# Q23_BRAKE_LIGHT.net
KiCad netlist of a schematic drawn in Altium Designer
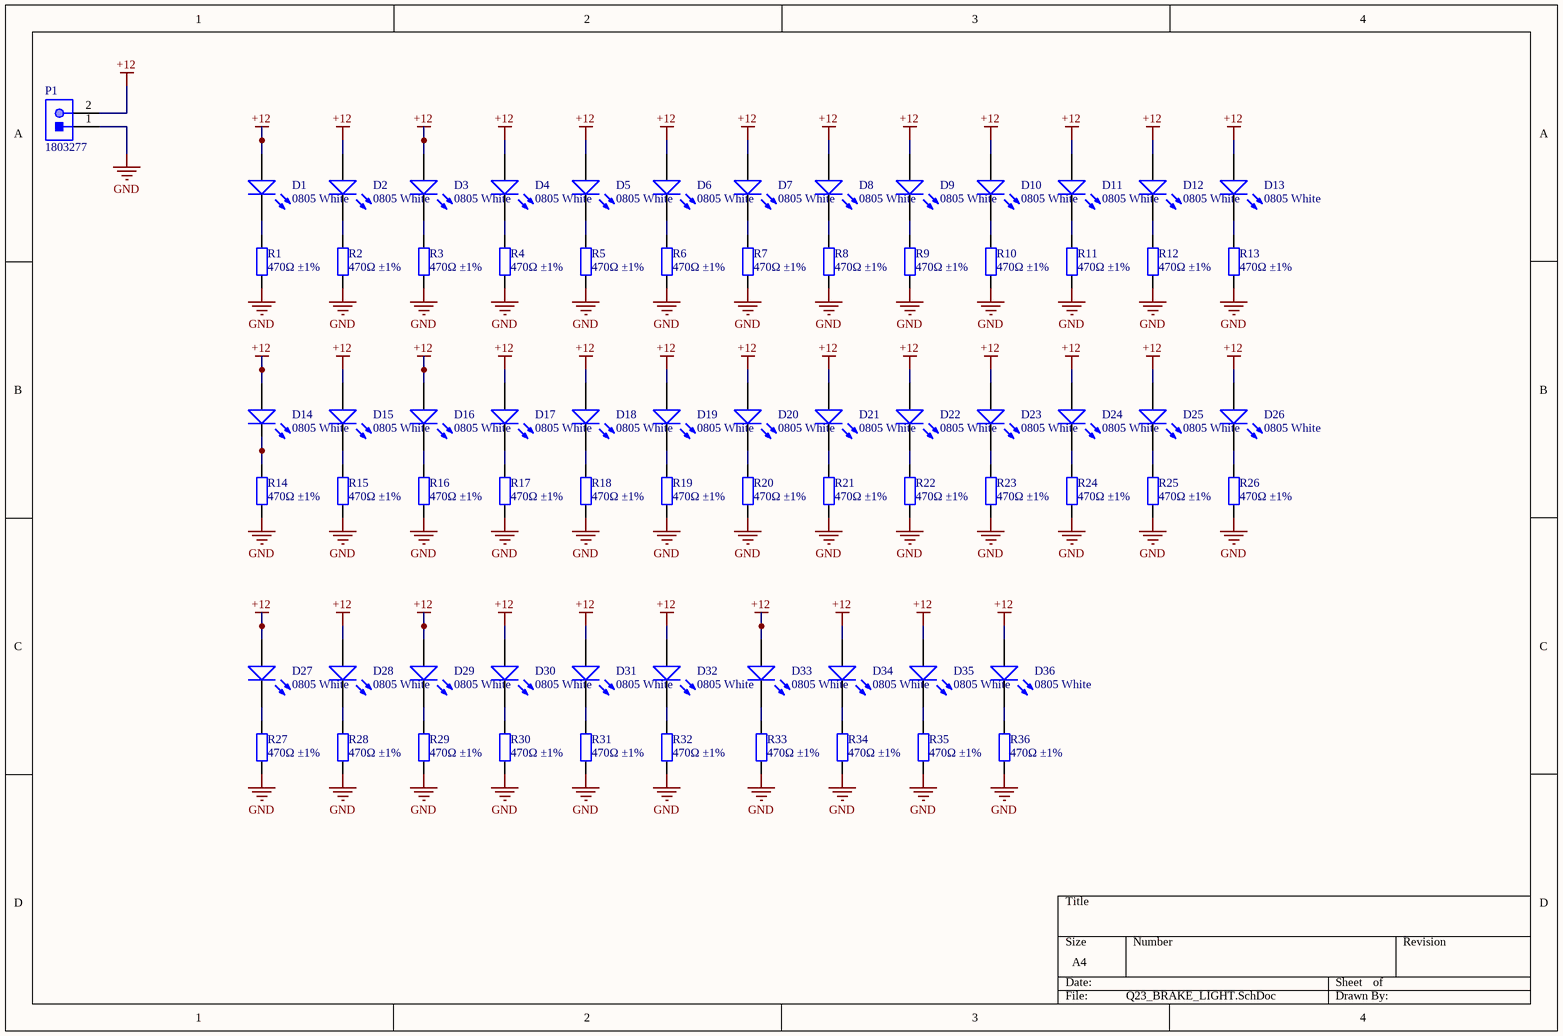
[diagram p0: Q23_BRAKE_LIGHT.SchDoc]

(export (version "E")
  (design (tool "Eeschema 10.0.6"))
  (components
    (comp (ref "D1")
      (value "0805 White")
      (footprint "0805_LED_S1")
      (description "LED")
      (libsource (lib "LED") (part "0805 LED White"))
    )
    (comp (ref "D2")
      (value "0805 White")
      (footprint "0805_LED_S1")
      (description "LED")
      (libsource (lib "LED") (part "0805 LED White"))
    )
    (comp (ref "D3")
      (value "0805 White")
      (footprint "0805_LED_S1")
      (description "LED")
      (libsource (lib "LED") (part "0805 LED White"))
    )
    (comp (ref "D4")
      (value "0805 White")
      (footprint "0805_LED_S1")
      (description "LED")
      (libsource (lib "LED") (part "0805 LED White"))
    )
    (comp (ref "D5")
      (value "0805 White")
      (footprint "0805_LED_S1")
      (description "LED")
      (libsource (lib "LED") (part "0805 LED White"))
    )
    (comp (ref "D6")
      (value "0805 White")
      (footprint "0805_LED_S1")
      (description "LED")
      (libsource (lib "LED") (part "0805 LED White"))
    )
    (comp (ref "D7")
      (value "0805 White")
      (footprint "0805_LED_S1")
      (description "LED")
      (libsource (lib "LED") (part "0805 LED White"))
    )
    (comp (ref "D8")
      (value "0805 White")
      (footprint "0805_LED_S1")
      (description "LED")
      (libsource (lib "LED") (part "0805 LED White"))
    )
    (comp (ref "D9")
      (value "0805 White")
      (footprint "0805_LED_S1")
      (description "LED")
      (libsource (lib "LED") (part "0805 LED White"))
    )
    (comp (ref "D10")
      (value "0805 White")
      (footprint "0805_LED_S1")
      (description "LED")
      (libsource (lib "LED") (part "0805 LED White"))
    )
    (comp (ref "D11")
      (value "0805 White")
      (footprint "0805_LED_S1")
      (description "LED")
      (libsource (lib "LED") (part "0805 LED White"))
    )
    (comp (ref "D12")
      (value "0805 White")
      (footprint "0805_LED_S1")
      (description "LED")
      (libsource (lib "LED") (part "0805 LED White"))
    )
    (comp (ref "D13")
      (value "0805 White")
      (footprint "0805_LED_S1")
      (description "LED")
      (libsource (lib "LED") (part "0805 LED White"))
    )
    (comp (ref "D14")
      (value "0805 White")
      (footprint "0805_LED_S1")
      (description "LED")
      (libsource (lib "LED") (part "0805 LED White"))
    )
    (comp (ref "D15")
      (value "0805 White")
      (footprint "0805_LED_S1")
      (description "LED")
      (libsource (lib "LED") (part "0805 LED White"))
    )
    (comp (ref "D16")
      (value "0805 White")
      (footprint "0805_LED_S1")
      (description "LED")
      (libsource (lib "LED") (part "0805 LED White"))
    )
    (comp (ref "D17")
      (value "0805 White")
      (footprint "0805_LED_S1")
      (description "LED")
      (libsource (lib "LED") (part "0805 LED White"))
    )
    (comp (ref "D18")
      (value "0805 White")
      (footprint "0805_LED_S1")
      (description "LED")
      (libsource (lib "LED") (part "0805 LED White"))
    )
    (comp (ref "D19")
      (value "0805 White")
      (footprint "0805_LED_S1")
      (description "LED")
      (libsource (lib "LED") (part "0805 LED White"))
    )
    (comp (ref "D20")
      (value "0805 White")
      (footprint "0805_LED_S1")
      (description "LED")
      (libsource (lib "LED") (part "0805 LED White"))
    )
    (comp (ref "D21")
      (value "0805 White")
      (footprint "0805_LED_S1")
      (description "LED")
      (libsource (lib "LED") (part "0805 LED White"))
    )
    (comp (ref "D22")
      (value "0805 White")
      (footprint "0805_LED_S1")
      (description "LED")
      (libsource (lib "LED") (part "0805 LED White"))
    )
    (comp (ref "D23")
      (value "0805 White")
      (footprint "0805_LED_S1")
      (description "LED")
      (libsource (lib "LED") (part "0805 LED White"))
    )
    (comp (ref "D24")
      (value "0805 White")
      (footprint "0805_LED_S1")
      (description "LED")
      (libsource (lib "LED") (part "0805 LED White"))
    )
    (comp (ref "D25")
      (value "0805 White")
      (footprint "0805_LED_S1")
      (description "LED")
      (libsource (lib "LED") (part "0805 LED White"))
    )
    (comp (ref "D26")
      (value "0805 White")
      (footprint "0805_LED_S1")
      (description "LED")
      (libsource (lib "LED") (part "0805 LED White"))
    )
    (comp (ref "D27")
      (value "0805 White")
      (footprint "0805_LED_S1")
      (description "LED")
      (libsource (lib "LED") (part "0805 LED White"))
    )
    (comp (ref "D28")
      (value "0805 White")
      (footprint "0805_LED_S1")
      (description "LED")
      (libsource (lib "LED") (part "0805 LED White"))
    )
    (comp (ref "D29")
      (value "0805 White")
      (footprint "0805_LED_S1")
      (description "LED")
      (libsource (lib "LED") (part "0805 LED White"))
    )
    (comp (ref "D30")
      (value "0805 White")
      (footprint "0805_LED_S1")
      (description "LED")
      (libsource (lib "LED") (part "0805 LED White"))
    )
    (comp (ref "D31")
      (value "0805 White")
      (footprint "0805_LED_S1")
      (description "LED")
      (libsource (lib "LED") (part "0805 LED White"))
    )
    (comp (ref "D32")
      (value "0805 White")
      (footprint "0805_LED_S1")
      (description "LED")
      (libsource (lib "LED") (part "0805 LED White"))
    )
    (comp (ref "D33")
      (value "0805 White")
      (footprint "0805_LED_S1")
      (description "LED")
      (libsource (lib "LED") (part "0805 LED White"))
    )
    (comp (ref "D34")
      (value "0805 White")
      (footprint "0805_LED_S1")
      (description "LED")
      (libsource (lib "LED") (part "0805 LED White"))
    )
    (comp (ref "D35")
      (value "0805 White")
      (footprint "0805_LED_S1")
      (description "LED")
      (libsource (lib "LED") (part "0805 LED White"))
    )
    (comp (ref "D36")
      (value "0805 White")
      (footprint "0805_LED_S1")
      (description "LED")
      (libsource (lib "LED") (part "0805 LED White"))
    )
    (comp (ref "P1")
      (value "1803277")
      (footprint "PHOE-1803277_V")
      (description "Male Header, Pitch 3.81 mm, 1 x 2 Position, Height 7.25 mm, Tail Length 3.4 mm, RoHS, Bulk")
      (fields (field (name "MANUFACTURER") "Phoenix Contact"))
      (libsource (lib "Americas- FSAE- Queens University") (part "CN-1P-M-R2"))
    )
    (comp (ref "R1")
      (value "470Ω ±1%")
      (footprint "0402_R")
      (description "Chip resistor")
      (fields (field (name "MANUFACTURER") "Uniroyal Elec") (field (name "PARTNUMBER") "0402WGF4700TCE"))
      (libsource (lib "RES") (part "0402 470R (4700) 1%"))
    )
    (comp (ref "R2")
      (value "470Ω ±1%")
      (footprint "0402_R")
      (description "Chip resistor")
      (fields (field (name "MANUFACTURER") "Uniroyal Elec") (field (name "PARTNUMBER") "0402WGF4700TCE"))
      (libsource (lib "RES") (part "0402 470R (4700) 1%"))
    )
    (comp (ref "R3")
      (value "470Ω ±1%")
      (footprint "0402_R")
      (description "Chip resistor")
      (fields (field (name "MANUFACTURER") "Uniroyal Elec") (field (name "PARTNUMBER") "0402WGF4700TCE"))
      (libsource (lib "RES") (part "0402 470R (4700) 1%"))
    )
    (comp (ref "R4")
      (value "470Ω ±1%")
      (footprint "0402_R")
      (description "Chip resistor")
      (fields (field (name "MANUFACTURER") "Uniroyal Elec") (field (name "PARTNUMBER") "0402WGF4700TCE"))
      (libsource (lib "RES") (part "0402 470R (4700) 1%"))
    )
    (comp (ref "R5")
      (value "470Ω ±1%")
      (footprint "0402_R")
      (description "Chip resistor")
      (fields (field (name "MANUFACTURER") "Uniroyal Elec") (field (name "PARTNUMBER") "0402WGF4700TCE"))
      (libsource (lib "RES") (part "0402 470R (4700) 1%"))
    )
    (comp (ref "R6")
      (value "470Ω ±1%")
      (footprint "0402_R")
      (description "Chip resistor")
      (fields (field (name "MANUFACTURER") "Uniroyal Elec") (field (name "PARTNUMBER") "0402WGF4700TCE"))
      (libsource (lib "RES") (part "0402 470R (4700) 1%"))
    )
    (comp (ref "R7")
      (value "470Ω ±1%")
      (footprint "0402_R")
      (description "Chip resistor")
      (fields (field (name "MANUFACTURER") "Uniroyal Elec") (field (name "PARTNUMBER") "0402WGF4700TCE"))
      (libsource (lib "RES") (part "0402 470R (4700) 1%"))
    )
    (comp (ref "R8")
      (value "470Ω ±1%")
      (footprint "0402_R")
      (description "Chip resistor")
      (fields (field (name "MANUFACTURER") "Uniroyal Elec") (field (name "PARTNUMBER") "0402WGF4700TCE"))
      (libsource (lib "RES") (part "0402 470R (4700) 1%"))
    )
    (comp (ref "R9")
      (value "470Ω ±1%")
      (footprint "0402_R")
      (description "Chip resistor")
      (fields (field (name "MANUFACTURER") "Uniroyal Elec") (field (name "PARTNUMBER") "0402WGF4700TCE"))
      (libsource (lib "RES") (part "0402 470R (4700) 1%"))
    )
    (comp (ref "R10")
      (value "470Ω ±1%")
      (footprint "0402_R")
      (description "Chip resistor")
      (fields (field (name "MANUFACTURER") "Uniroyal Elec") (field (name "PARTNUMBER") "0402WGF4700TCE"))
      (libsource (lib "RES") (part "0402 470R (4700) 1%"))
    )
    (comp (ref "R11")
      (value "470Ω ±1%")
      (footprint "0402_R")
      (description "Chip resistor")
      (fields (field (name "MANUFACTURER") "Uniroyal Elec") (field (name "PARTNUMBER") "0402WGF4700TCE"))
      (libsource (lib "RES") (part "0402 470R (4700) 1%"))
    )
    (comp (ref "R12")
      (value "470Ω ±1%")
      (footprint "0402_R")
      (description "Chip resistor")
      (fields (field (name "MANUFACTURER") "Uniroyal Elec") (field (name "PARTNUMBER") "0402WGF4700TCE"))
      (libsource (lib "RES") (part "0402 470R (4700) 1%"))
    )
    (comp (ref "R13")
      (value "470Ω ±1%")
      (footprint "0402_R")
      (description "Chip resistor")
      (fields (field (name "MANUFACTURER") "Uniroyal Elec") (field (name "PARTNUMBER") "0402WGF4700TCE"))
      (libsource (lib "RES") (part "0402 470R (4700) 1%"))
    )
    (comp (ref "R14")
      (value "470Ω ±1%")
      (footprint "0402_R")
      (description "Chip resistor")
      (fields (field (name "MANUFACTURER") "Uniroyal Elec") (field (name "PARTNUMBER") "0402WGF4700TCE"))
      (libsource (lib "RES") (part "0402 470R (4700) 1%"))
    )
    (comp (ref "R15")
      (value "470Ω ±1%")
      (footprint "0402_R")
      (description "Chip resistor")
      (fields (field (name "MANUFACTURER") "Uniroyal Elec") (field (name "PARTNUMBER") "0402WGF4700TCE"))
      (libsource (lib "RES") (part "0402 470R (4700) 1%"))
    )
    (comp (ref "R16")
      (value "470Ω ±1%")
      (footprint "0402_R")
      (description "Chip resistor")
      (fields (field (name "MANUFACTURER") "Uniroyal Elec") (field (name "PARTNUMBER") "0402WGF4700TCE"))
      (libsource (lib "RES") (part "0402 470R (4700) 1%"))
    )
    (comp (ref "R17")
      (value "470Ω ±1%")
      (footprint "0402_R")
      (description "Chip resistor")
      (fields (field (name "MANUFACTURER") "Uniroyal Elec") (field (name "PARTNUMBER") "0402WGF4700TCE"))
      (libsource (lib "RES") (part "0402 470R (4700) 1%"))
    )
    (comp (ref "R18")
      (value "470Ω ±1%")
      (footprint "0402_R")
      (description "Chip resistor")
      (fields (field (name "MANUFACTURER") "Uniroyal Elec") (field (name "PARTNUMBER") "0402WGF4700TCE"))
      (libsource (lib "RES") (part "0402 470R (4700) 1%"))
    )
    (comp (ref "R19")
      (value "470Ω ±1%")
      (footprint "0402_R")
      (description "Chip resistor")
      (fields (field (name "MANUFACTURER") "Uniroyal Elec") (field (name "PARTNUMBER") "0402WGF4700TCE"))
      (libsource (lib "RES") (part "0402 470R (4700) 1%"))
    )
    (comp (ref "R20")
      (value "470Ω ±1%")
      (footprint "0402_R")
      (description "Chip resistor")
      (fields (field (name "MANUFACTURER") "Uniroyal Elec") (field (name "PARTNUMBER") "0402WGF4700TCE"))
      (libsource (lib "RES") (part "0402 470R (4700) 1%"))
    )
    (comp (ref "R21")
      (value "470Ω ±1%")
      (footprint "0402_R")
      (description "Chip resistor")
      (fields (field (name "MANUFACTURER") "Uniroyal Elec") (field (name "PARTNUMBER") "0402WGF4700TCE"))
      (libsource (lib "RES") (part "0402 470R (4700) 1%"))
    )
    (comp (ref "R22")
      (value "470Ω ±1%")
      (footprint "0402_R")
      (description "Chip resistor")
      (fields (field (name "MANUFACTURER") "Uniroyal Elec") (field (name "PARTNUMBER") "0402WGF4700TCE"))
      (libsource (lib "RES") (part "0402 470R (4700) 1%"))
    )
    (comp (ref "R23")
      (value "470Ω ±1%")
      (footprint "0402_R")
      (description "Chip resistor")
      (fields (field (name "MANUFACTURER") "Uniroyal Elec") (field (name "PARTNUMBER") "0402WGF4700TCE"))
      (libsource (lib "RES") (part "0402 470R (4700) 1%"))
    )
    (comp (ref "R24")
      (value "470Ω ±1%")
      (footprint "0402_R")
      (description "Chip resistor")
      (fields (field (name "MANUFACTURER") "Uniroyal Elec") (field (name "PARTNUMBER") "0402WGF4700TCE"))
      (libsource (lib "RES") (part "0402 470R (4700) 1%"))
    )
    (comp (ref "R25")
      (value "470Ω ±1%")
      (footprint "0402_R")
      (description "Chip resistor")
      (fields (field (name "MANUFACTURER") "Uniroyal Elec") (field (name "PARTNUMBER") "0402WGF4700TCE"))
      (libsource (lib "RES") (part "0402 470R (4700) 1%"))
    )
    (comp (ref "R26")
      (value "470Ω ±1%")
      (footprint "0402_R")
      (description "Chip resistor")
      (fields (field (name "MANUFACTURER") "Uniroyal Elec") (field (name "PARTNUMBER") "0402WGF4700TCE"))
      (libsource (lib "RES") (part "0402 470R (4700) 1%"))
    )
    (comp (ref "R27")
      (value "470Ω ±1%")
      (footprint "0402_R")
      (description "Chip resistor")
      (fields (field (name "MANUFACTURER") "Uniroyal Elec") (field (name "PARTNUMBER") "0402WGF4700TCE"))
      (libsource (lib "RES") (part "0402 470R (4700) 1%"))
    )
    (comp (ref "R28")
      (value "470Ω ±1%")
      (footprint "0402_R")
      (description "Chip resistor")
      (fields (field (name "MANUFACTURER") "Uniroyal Elec") (field (name "PARTNUMBER") "0402WGF4700TCE"))
      (libsource (lib "RES") (part "0402 470R (4700) 1%"))
    )
    (comp (ref "R29")
      (value "470Ω ±1%")
      (footprint "0402_R")
      (description "Chip resistor")
      (fields (field (name "MANUFACTURER") "Uniroyal Elec") (field (name "PARTNUMBER") "0402WGF4700TCE"))
      (libsource (lib "RES") (part "0402 470R (4700) 1%"))
    )
    (comp (ref "R30")
      (value "470Ω ±1%")
      (footprint "0402_R")
      (description "Chip resistor")
      (fields (field (name "MANUFACTURER") "Uniroyal Elec") (field (name "PARTNUMBER") "0402WGF4700TCE"))
      (libsource (lib "RES") (part "0402 470R (4700) 1%"))
    )
    (comp (ref "R31")
      (value "470Ω ±1%")
      (footprint "0402_R")
      (description "Chip resistor")
      (fields (field (name "MANUFACTURER") "Uniroyal Elec") (field (name "PARTNUMBER") "0402WGF4700TCE"))
      (libsource (lib "RES") (part "0402 470R (4700) 1%"))
    )
    (comp (ref "R32")
      (value "470Ω ±1%")
      (footprint "0402_R")
      (description "Chip resistor")
      (fields (field (name "MANUFACTURER") "Uniroyal Elec") (field (name "PARTNUMBER") "0402WGF4700TCE"))
      (libsource (lib "RES") (part "0402 470R (4700) 1%"))
    )
    (comp (ref "R33")
      (value "470Ω ±1%")
      (footprint "0402_R")
      (description "Chip resistor")
      (fields (field (name "MANUFACTURER") "Uniroyal Elec") (field (name "PARTNUMBER") "0402WGF4700TCE"))
      (libsource (lib "RES") (part "0402 470R (4700) 1%"))
    )
    (comp (ref "R34")
      (value "470Ω ±1%")
      (footprint "0402_R")
      (description "Chip resistor")
      (fields (field (name "MANUFACTURER") "Uniroyal Elec") (field (name "PARTNUMBER") "0402WGF4700TCE"))
      (libsource (lib "RES") (part "0402 470R (4700) 1%"))
    )
    (comp (ref "R35")
      (value "470Ω ±1%")
      (footprint "0402_R")
      (description "Chip resistor")
      (fields (field (name "MANUFACTURER") "Uniroyal Elec") (field (name "PARTNUMBER") "0402WGF4700TCE"))
      (libsource (lib "RES") (part "0402 470R (4700) 1%"))
    )
    (comp (ref "R36")
      (value "470Ω ±1%")
      (footprint "0402_R")
      (description "Chip resistor")
      (fields (field (name "MANUFACTURER") "Uniroyal Elec") (field (name "PARTNUMBER") "0402WGF4700TCE"))
      (libsource (lib "RES") (part "0402 470R (4700) 1%"))
    )
  )
  (nets
    (net (code "1") (name "+12") (class "Default")
      (node (ref "D1") (pin "A") (pinfunction "A_A") (pintype "passive"))
      (node (ref "D10") (pin "A") (pinfunction "A_A") (pintype "passive"))
      (node (ref "D11") (pin "A") (pinfunction "A_A") (pintype "passive"))
      (node (ref "D12") (pin "A") (pinfunction "A_A") (pintype "passive"))
      (node (ref "D13") (pin "A") (pinfunction "A_A") (pintype "passive"))
      (node (ref "D14") (pin "A") (pinfunction "A_A") (pintype "passive"))
      (node (ref "D15") (pin "A") (pinfunction "A_A") (pintype "passive"))
      (node (ref "D16") (pin "A") (pinfunction "A_A") (pintype "passive"))
      (node (ref "D17") (pin "A") (pinfunction "A_A") (pintype "passive"))
      (node (ref "D18") (pin "A") (pinfunction "A_A") (pintype "passive"))
      (node (ref "D19") (pin "A") (pinfunction "A_A") (pintype "passive"))
      (node (ref "D2") (pin "A") (pinfunction "A_A") (pintype "passive"))
      (node (ref "D20") (pin "A") (pinfunction "A_A") (pintype "passive"))
      (node (ref "D21") (pin "A") (pinfunction "A_A") (pintype "passive"))
      (node (ref "D22") (pin "A") (pinfunction "A_A") (pintype "passive"))
      (node (ref "D23") (pin "A") (pinfunction "A_A") (pintype "passive"))
      (node (ref "D24") (pin "A") (pinfunction "A_A") (pintype "passive"))
      (node (ref "D25") (pin "A") (pinfunction "A_A") (pintype "passive"))
      (node (ref "D26") (pin "A") (pinfunction "A_A") (pintype "passive"))
      (node (ref "D27") (pin "A") (pinfunction "A_A") (pintype "passive"))
      (node (ref "D28") (pin "A") (pinfunction "A_A") (pintype "passive"))
      (node (ref "D29") (pin "A") (pinfunction "A_A") (pintype "passive"))
      (node (ref "D3") (pin "A") (pinfunction "A_A") (pintype "passive"))
      (node (ref "D30") (pin "A") (pinfunction "A_A") (pintype "passive"))
      (node (ref "D31") (pin "A") (pinfunction "A_A") (pintype "passive"))
      (node (ref "D32") (pin "A") (pinfunction "A_A") (pintype "passive"))
      (node (ref "D33") (pin "A") (pinfunction "A_A") (pintype "passive"))
      (node (ref "D34") (pin "A") (pinfunction "A_A") (pintype "passive"))
      (node (ref "D35") (pin "A") (pinfunction "A_A") (pintype "passive"))
      (node (ref "D36") (pin "A") (pinfunction "A_A") (pintype "passive"))
      (node (ref "D4") (pin "A") (pinfunction "A_A") (pintype "passive"))
      (node (ref "D5") (pin "A") (pinfunction "A_A") (pintype "passive"))
      (node (ref "D6") (pin "A") (pinfunction "A_A") (pintype "passive"))
      (node (ref "D7") (pin "A") (pinfunction "A_A") (pintype "passive"))
      (node (ref "D8") (pin "A") (pinfunction "A_A") (pintype "passive"))
      (node (ref "D9") (pin "A") (pinfunction "A_A") (pintype "passive"))
      (node (ref "P1") (pin "2") (pinfunction "2_2") (pintype "passive"))
    )
    (net (code "2") (name "GND") (class "Default")
      (node (ref "P1") (pin "1") (pinfunction "1_1") (pintype "passive"))
      (node (ref "R1") (pin "1") (pinfunction "1_1") (pintype "passive"))
      (node (ref "R10") (pin "1") (pinfunction "1_1") (pintype "passive"))
      (node (ref "R11") (pin "1") (pinfunction "1_1") (pintype "passive"))
      (node (ref "R12") (pin "1") (pinfunction "1_1") (pintype "passive"))
      (node (ref "R13") (pin "1") (pinfunction "1_1") (pintype "passive"))
      (node (ref "R14") (pin "1") (pinfunction "1_1") (pintype "passive"))
      (node (ref "R15") (pin "1") (pinfunction "1_1") (pintype "passive"))
      (node (ref "R16") (pin "1") (pinfunction "1_1") (pintype "passive"))
      (node (ref "R17") (pin "1") (pinfunction "1_1") (pintype "passive"))
      (node (ref "R18") (pin "1") (pinfunction "1_1") (pintype "passive"))
      (node (ref "R19") (pin "1") (pinfunction "1_1") (pintype "passive"))
      (node (ref "R2") (pin "1") (pinfunction "1_1") (pintype "passive"))
      (node (ref "R20") (pin "1") (pinfunction "1_1") (pintype "passive"))
      (node (ref "R21") (pin "1") (pinfunction "1_1") (pintype "passive"))
      (node (ref "R22") (pin "1") (pinfunction "1_1") (pintype "passive"))
      (node (ref "R23") (pin "1") (pinfunction "1_1") (pintype "passive"))
      (node (ref "R24") (pin "1") (pinfunction "1_1") (pintype "passive"))
      (node (ref "R25") (pin "1") (pinfunction "1_1") (pintype "passive"))
      (node (ref "R26") (pin "1") (pinfunction "1_1") (pintype "passive"))
      (node (ref "R27") (pin "1") (pinfunction "1_1") (pintype "passive"))
      (node (ref "R28") (pin "1") (pinfunction "1_1") (pintype "passive"))
      (node (ref "R29") (pin "1") (pinfunction "1_1") (pintype "passive"))
      (node (ref "R3") (pin "1") (pinfunction "1_1") (pintype "passive"))
      (node (ref "R30") (pin "1") (pinfunction "1_1") (pintype "passive"))
      (node (ref "R31") (pin "1") (pinfunction "1_1") (pintype "passive"))
      (node (ref "R32") (pin "1") (pinfunction "1_1") (pintype "passive"))
      (node (ref "R33") (pin "1") (pinfunction "1_1") (pintype "passive"))
      (node (ref "R34") (pin "1") (pinfunction "1_1") (pintype "passive"))
      (node (ref "R35") (pin "1") (pinfunction "1_1") (pintype "passive"))
      (node (ref "R36") (pin "1") (pinfunction "1_1") (pintype "passive"))
      (node (ref "R4") (pin "1") (pinfunction "1_1") (pintype "passive"))
      (node (ref "R5") (pin "1") (pinfunction "1_1") (pintype "passive"))
      (node (ref "R6") (pin "1") (pinfunction "1_1") (pintype "passive"))
      (node (ref "R7") (pin "1") (pinfunction "1_1") (pintype "passive"))
      (node (ref "R8") (pin "1") (pinfunction "1_1") (pintype "passive"))
      (node (ref "R9") (pin "1") (pinfunction "1_1") (pintype "passive"))
    )
    (net (code "3") (name "Net-(D1-PadK)") (class "Default")
      (node (ref "D1") (pin "K") (pinfunction "K_K") (pintype "passive"))
      (node (ref "R1") (pin "2") (pinfunction "2_2") (pintype "passive"))
    )
    (net (code "4") (name "Net-(D2-PadK)") (class "Default")
      (node (ref "D2") (pin "K") (pinfunction "K_K") (pintype "passive"))
      (node (ref "R2") (pin "2") (pinfunction "2_2") (pintype "passive"))
    )
    (net (code "5") (name "Net-(D3-PadK)") (class "Default")
      (node (ref "D3") (pin "K") (pinfunction "K_K") (pintype "passive"))
      (node (ref "R3") (pin "2") (pinfunction "2_2") (pintype "passive"))
    )
    (net (code "6") (name "Net-(D4-PadK)") (class "Default")
      (node (ref "D4") (pin "K") (pinfunction "K_K") (pintype "passive"))
      (node (ref "R4") (pin "2") (pinfunction "2_2") (pintype "passive"))
    )
    (net (code "7") (name "Net-(D5-PadK)") (class "Default")
      (node (ref "D5") (pin "K") (pinfunction "K_K") (pintype "passive"))
      (node (ref "R5") (pin "2") (pinfunction "2_2") (pintype "passive"))
    )
    (net (code "8") (name "Net-(D6-PadK)") (class "Default")
      (node (ref "D6") (pin "K") (pinfunction "K_K") (pintype "passive"))
      (node (ref "R6") (pin "2") (pinfunction "2_2") (pintype "passive"))
    )
    (net (code "9") (name "Net-(D7-PadK)") (class "Default")
      (node (ref "D7") (pin "K") (pinfunction "K_K") (pintype "passive"))
      (node (ref "R7") (pin "2") (pinfunction "2_2") (pintype "passive"))
    )
    (net (code "10") (name "Net-(D8-PadK)") (class "Default")
      (node (ref "D8") (pin "K") (pinfunction "K_K") (pintype "passive"))
      (node (ref "R8") (pin "2") (pinfunction "2_2") (pintype "passive"))
    )
    (net (code "11") (name "Net-(D9-PadK)") (class "Default")
      (node (ref "D9") (pin "K") (pinfunction "K_K") (pintype "passive"))
      (node (ref "R9") (pin "2") (pinfunction "2_2") (pintype "passive"))
    )
    (net (code "12") (name "Net-(D10-PadK)") (class "Default")
      (node (ref "D10") (pin "K") (pinfunction "K_K") (pintype "passive"))
      (node (ref "R10") (pin "2") (pinfunction "2_2") (pintype "passive"))
    )
    (net (code "13") (name "Net-(D11-PadK)") (class "Default")
      (node (ref "D11") (pin "K") (pinfunction "K_K") (pintype "passive"))
      (node (ref "R11") (pin "2") (pinfunction "2_2") (pintype "passive"))
    )
    (net (code "14") (name "Net-(D12-PadK)") (class "Default")
      (node (ref "D12") (pin "K") (pinfunction "K_K") (pintype "passive"))
      (node (ref "R12") (pin "2") (pinfunction "2_2") (pintype "passive"))
    )
    (net (code "15") (name "Net-(D13-PadK)") (class "Default")
      (node (ref "D13") (pin "K") (pinfunction "K_K") (pintype "passive"))
      (node (ref "R13") (pin "2") (pinfunction "2_2") (pintype "passive"))
    )
    (net (code "16") (name "Net-(D14-PadK)") (class "Default")
      (node (ref "D14") (pin "K") (pinfunction "K_K") (pintype "passive"))
      (node (ref "R14") (pin "2") (pinfunction "2_2") (pintype "passive"))
    )
    (net (code "17") (name "Net-(D15-PadK)") (class "Default")
      (node (ref "D15") (pin "K") (pinfunction "K_K") (pintype "passive"))
      (node (ref "R15") (pin "2") (pinfunction "2_2") (pintype "passive"))
    )
    (net (code "18") (name "Net-(D16-PadK)") (class "Default")
      (node (ref "D16") (pin "K") (pinfunction "K_K") (pintype "passive"))
      (node (ref "R16") (pin "2") (pinfunction "2_2") (pintype "passive"))
    )
    (net (code "19") (name "Net-(D17-PadK)") (class "Default")
      (node (ref "D17") (pin "K") (pinfunction "K_K") (pintype "passive"))
      (node (ref "R17") (pin "2") (pinfunction "2_2") (pintype "passive"))
    )
    (net (code "20") (name "Net-(D18-PadK)") (class "Default")
      (node (ref "D18") (pin "K") (pinfunction "K_K") (pintype "passive"))
      (node (ref "R18") (pin "2") (pinfunction "2_2") (pintype "passive"))
    )
    (net (code "21") (name "Net-(D19-PadK)") (class "Default")
      (node (ref "D19") (pin "K") (pinfunction "K_K") (pintype "passive"))
      (node (ref "R19") (pin "2") (pinfunction "2_2") (pintype "passive"))
    )
    (net (code "22") (name "Net-(D20-PadK)") (class "Default")
      (node (ref "D20") (pin "K") (pinfunction "K_K") (pintype "passive"))
      (node (ref "R20") (pin "2") (pinfunction "2_2") (pintype "passive"))
    )
    (net (code "23") (name "Net-(D21-PadK)") (class "Default")
      (node (ref "D21") (pin "K") (pinfunction "K_K") (pintype "passive"))
      (node (ref "R21") (pin "2") (pinfunction "2_2") (pintype "passive"))
    )
    (net (code "24") (name "Net-(D22-PadK)") (class "Default")
      (node (ref "D22") (pin "K") (pinfunction "K_K") (pintype "passive"))
      (node (ref "R22") (pin "2") (pinfunction "2_2") (pintype "passive"))
    )
    (net (code "25") (name "Net-(D23-PadK)") (class "Default")
      (node (ref "D23") (pin "K") (pinfunction "K_K") (pintype "passive"))
      (node (ref "R23") (pin "2") (pinfunction "2_2") (pintype "passive"))
    )
    (net (code "26") (name "Net-(D24-PadK)") (class "Default")
      (node (ref "D24") (pin "K") (pinfunction "K_K") (pintype "passive"))
      (node (ref "R24") (pin "2") (pinfunction "2_2") (pintype "passive"))
    )
    (net (code "27") (name "Net-(D25-PadK)") (class "Default")
      (node (ref "D25") (pin "K") (pinfunction "K_K") (pintype "passive"))
      (node (ref "R25") (pin "2") (pinfunction "2_2") (pintype "passive"))
    )
    (net (code "28") (name "Net-(D26-PadK)") (class "Default")
      (node (ref "D26") (pin "K") (pinfunction "K_K") (pintype "passive"))
      (node (ref "R26") (pin "2") (pinfunction "2_2") (pintype "passive"))
    )
    (net (code "29") (name "Net-(D27-PadK)") (class "Default")
      (node (ref "D27") (pin "K") (pinfunction "K_K") (pintype "passive"))
      (node (ref "R27") (pin "2") (pinfunction "2_2") (pintype "passive"))
    )
    (net (code "30") (name "Net-(D28-PadK)") (class "Default")
      (node (ref "D28") (pin "K") (pinfunction "K_K") (pintype "passive"))
      (node (ref "R28") (pin "2") (pinfunction "2_2") (pintype "passive"))
    )
    (net (code "31") (name "Net-(D29-PadK)") (class "Default")
      (node (ref "D29") (pin "K") (pinfunction "K_K") (pintype "passive"))
      (node (ref "R29") (pin "2") (pinfunction "2_2") (pintype "passive"))
    )
    (net (code "32") (name "Net-(D30-PadK)") (class "Default")
      (node (ref "D30") (pin "K") (pinfunction "K_K") (pintype "passive"))
      (node (ref "R30") (pin "2") (pinfunction "2_2") (pintype "passive"))
    )
    (net (code "33") (name "Net-(D31-PadK)") (class "Default")
      (node (ref "D31") (pin "K") (pinfunction "K_K") (pintype "passive"))
      (node (ref "R31") (pin "2") (pinfunction "2_2") (pintype "passive"))
    )
    (net (code "34") (name "Net-(D32-PadK)") (class "Default")
      (node (ref "D32") (pin "K") (pinfunction "K_K") (pintype "passive"))
      (node (ref "R32") (pin "2") (pinfunction "2_2") (pintype "passive"))
    )
    (net (code "35") (name "Net-(D33-PadK)") (class "Default")
      (node (ref "D33") (pin "K") (pinfunction "K_K") (pintype "passive"))
      (node (ref "R33") (pin "2") (pinfunction "2_2") (pintype "passive"))
    )
    (net (code "36") (name "Net-(D34-PadK)") (class "Default")
      (node (ref "D34") (pin "K") (pinfunction "K_K") (pintype "passive"))
      (node (ref "R34") (pin "2") (pinfunction "2_2") (pintype "passive"))
    )
    (net (code "37") (name "Net-(D35-PadK)") (class "Default")
      (node (ref "D35") (pin "K") (pinfunction "K_K") (pintype "passive"))
      (node (ref "R35") (pin "2") (pinfunction "2_2") (pintype "passive"))
    )
    (net (code "38") (name "Net-(D36-PadK)") (class "Default")
      (node (ref "D36") (pin "K") (pinfunction "K_K") (pintype "passive"))
      (node (ref "R36") (pin "2") (pinfunction "2_2") (pintype "passive"))
    )
  )
)
